# Eingangsstufe.net
KiCad netlist of a schematic drawn in Altium Designer
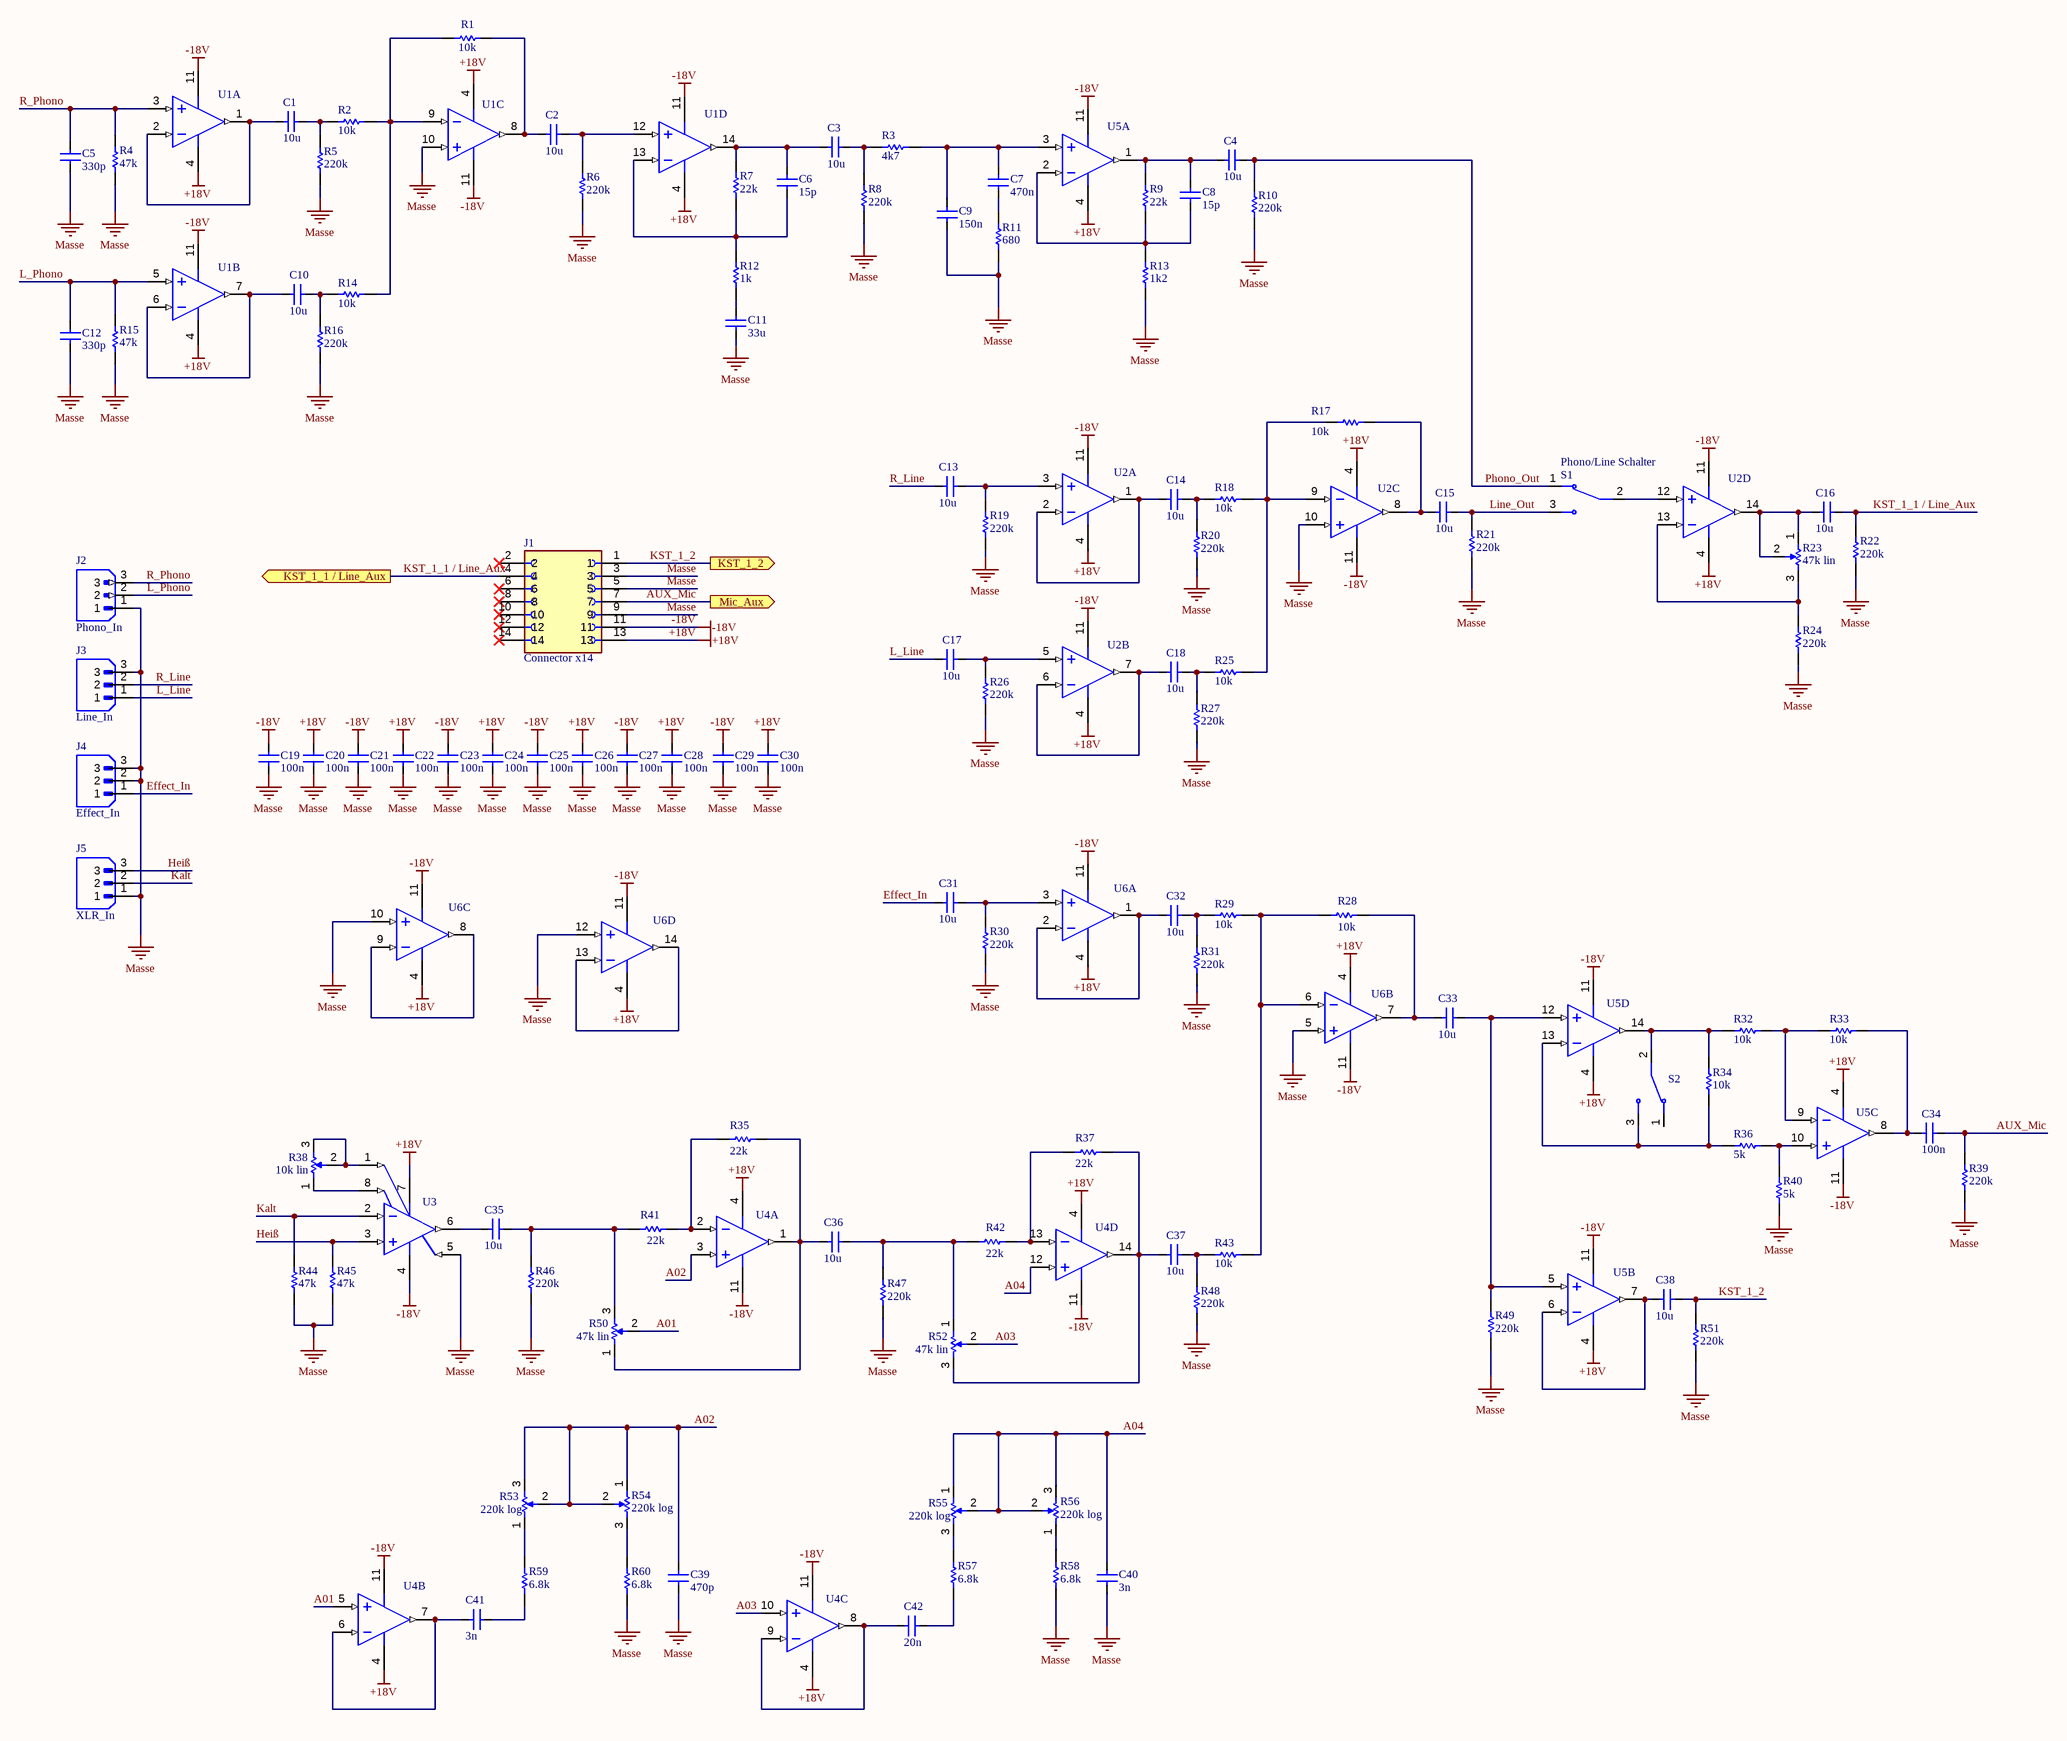
[diagram p0: Eingangsstufe.SchDoc]

(export (version "E")
  (design (tool "Eeschema 10.0.6"))
  (components
    (comp (ref "C1")
      (value "10u")
      (footprint "0805")
      (description "0805 Kondensator")
      (libsource (lib "Bauteile") (part "0805 Kondensator"))
    )
    (comp (ref "C2")
      (value "10u")
      (footprint "0805")
      (description "0805 Kondensator")
      (libsource (lib "Bauteile") (part "0805 Kondensator"))
    )
    (comp (ref "C3")
      (value "10u")
      (footprint "0805")
      (description "0805 Kondensator")
      (libsource (lib "Bauteile") (part "0805 Kondensator"))
    )
    (comp (ref "C4")
      (value "10u")
      (footprint "0805")
      (description "0805 Kondensator")
      (libsource (lib "Bauteile") (part "0805 Kondensator"))
    )
    (comp (ref "C5")
      (value "330p")
      (footprint "0805")
      (description "0805 Kondensator")
      (libsource (lib "Bauteile") (part "0805 Kondensator"))
    )
    (comp (ref "C6")
      (value "15p")
      (footprint "0805")
      (description "0805 Kondensator")
      (libsource (lib "Bauteile") (part "0805 Kondensator"))
    )
    (comp (ref "C7")
      (value "470n")
      (footprint "0805")
      (description "0805 Kondensator")
      (libsource (lib "Bauteile") (part "0805 Kondensator"))
    )
    (comp (ref "C8")
      (value "15p")
      (footprint "0805")
      (description "0805 Kondensator")
      (libsource (lib "Bauteile") (part "0805 Kondensator"))
    )
    (comp (ref "C9")
      (value "150n")
      (footprint "0805")
      (description "0805 Kondensator")
      (libsource (lib "Bauteile") (part "0805 Kondensator"))
    )
    (comp (ref "C10")
      (value "10u")
      (footprint "0805")
      (description "0805 Kondensator")
      (libsource (lib "Bauteile") (part "0805 Kondensator"))
    )
    (comp (ref "C11")
      (value "33u")
      (footprint "0805")
      (description "0805 Kondensator")
      (libsource (lib "Bauteile") (part "0805 Kondensator"))
    )
    (comp (ref "C12")
      (value "330p")
      (footprint "0805")
      (description "0805 Kondensator")
      (libsource (lib "Bauteile") (part "0805 Kondensator"))
    )
    (comp (ref "C13")
      (value "10u")
      (footprint "0805")
      (description "0805 Kondensator")
      (libsource (lib "Bauteile") (part "0805 Kondensator"))
    )
    (comp (ref "C14")
      (value "10u")
      (footprint "0805")
      (description "0805 Kondensator")
      (libsource (lib "Bauteile") (part "0805 Kondensator"))
    )
    (comp (ref "C15")
      (value "10u")
      (footprint "0805")
      (description "0805 Kondensator")
      (libsource (lib "Bauteile") (part "0805 Kondensator"))
    )
    (comp (ref "C16")
      (value "10u")
      (footprint "0805")
      (description "0805 Kondensator")
      (libsource (lib "Bauteile") (part "0805 Kondensator"))
    )
    (comp (ref "C17")
      (value "10u")
      (footprint "0805")
      (description "0805 Kondensator")
      (libsource (lib "Bauteile") (part "0805 Kondensator"))
    )
    (comp (ref "C18")
      (value "10u")
      (footprint "0805")
      (description "0805 Kondensator")
      (libsource (lib "Bauteile") (part "0805 Kondensator"))
    )
    (comp (ref "C19")
      (value "100n")
      (footprint "0805")
      (description "0805 Kondensator")
      (libsource (lib "Bauteile") (part "0805 Kondensator"))
    )
    (comp (ref "C20")
      (value "100n")
      (footprint "0805")
      (description "0805 Kondensator")
      (libsource (lib "Bauteile") (part "0805 Kondensator"))
    )
    (comp (ref "C21")
      (value "100n")
      (footprint "0805")
      (description "0805 Kondensator")
      (libsource (lib "Bauteile") (part "0805 Kondensator"))
    )
    (comp (ref "C22")
      (value "100n")
      (footprint "0805")
      (description "0805 Kondensator")
      (libsource (lib "Bauteile") (part "0805 Kondensator"))
    )
    (comp (ref "C23")
      (value "100n")
      (footprint "0805")
      (description "0805 Kondensator")
      (libsource (lib "Bauteile") (part "0805 Kondensator"))
    )
    (comp (ref "C24")
      (value "100n")
      (footprint "0805")
      (description "0805 Kondensator")
      (libsource (lib "Bauteile") (part "0805 Kondensator"))
    )
    (comp (ref "C25")
      (value "100n")
      (footprint "0805")
      (description "0805 Kondensator")
      (libsource (lib "Bauteile") (part "0805 Kondensator"))
    )
    (comp (ref "C26")
      (value "100n")
      (footprint "0805")
      (description "0805 Kondensator")
      (libsource (lib "Bauteile") (part "0805 Kondensator"))
    )
    (comp (ref "C27")
      (value "100n")
      (footprint "0805")
      (description "0805 Kondensator")
      (libsource (lib "Bauteile") (part "0805 Kondensator"))
    )
    (comp (ref "C28")
      (value "100n")
      (footprint "0805")
      (description "0805 Kondensator")
      (libsource (lib "Bauteile") (part "0805 Kondensator"))
    )
    (comp (ref "C29")
      (value "100n")
      (footprint "0805")
      (description "0805 Kondensator")
      (libsource (lib "Bauteile") (part "0805 Kondensator"))
    )
    (comp (ref "C30")
      (value "100n")
      (footprint "0805")
      (description "0805 Kondensator")
      (libsource (lib "Bauteile") (part "0805 Kondensator"))
    )
    (comp (ref "C31")
      (value "10u")
      (footprint "0805")
      (description "0805 Kondensator")
      (libsource (lib "Bauteile") (part "0805 Kondensator"))
    )
    (comp (ref "C32")
      (value "10u")
      (footprint "0805")
      (description "0805 Kondensator")
      (libsource (lib "Bauteile") (part "0805 Kondensator"))
    )
    (comp (ref "C33")
      (value "10u")
      (footprint "0805")
      (description "0805 Kondensator")
      (libsource (lib "Bauteile") (part "0805 Kondensator"))
    )
    (comp (ref "C34")
      (value "100n")
      (footprint "0805")
      (description "0805 Kondensator")
      (libsource (lib "Bauteile") (part "0805 Kondensator"))
    )
    (comp (ref "C35")
      (value "10u")
      (footprint "0805")
      (description "0805 Kondensator")
      (libsource (lib "Bauteile") (part "0805 Kondensator"))
    )
    (comp (ref "C36")
      (value "10u")
      (footprint "0805")
      (description "0805 Kondensator")
      (libsource (lib "Bauteile") (part "0805 Kondensator"))
    )
    (comp (ref "C37")
      (value "10u")
      (footprint "0805")
      (description "0805 Kondensator")
      (libsource (lib "Bauteile") (part "0805 Kondensator"))
    )
    (comp (ref "C38")
      (value "10u")
      (footprint "0805")
      (description "0805 Kondensator")
      (libsource (lib "Bauteile") (part "0805 Kondensator"))
    )
    (comp (ref "C39")
      (value "470p")
      (footprint "0805")
      (description "0805 Kondensator")
      (libsource (lib "Bauteile") (part "0805 Kondensator"))
    )
    (comp (ref "C40")
      (value "3n")
      (footprint "0805")
      (description "0805 Kondensator")
      (libsource (lib "Bauteile") (part "0805 Kondensator"))
    )
    (comp (ref "C41")
      (value "3n")
      (footprint "0805")
      (description "0805 Kondensator")
      (libsource (lib "Bauteile") (part "0805 Kondensator"))
    )
    (comp (ref "C42")
      (value "20n")
      (footprint "0805")
      (description "0805 Kondensator")
      (libsource (lib "Bauteile") (part "0805 Kondensator"))
    )
    (comp (ref "J1")
      (value "Connector x14")
      (footprint "Connector x14")
      (description "14 Position Header Connector Through Hole")
      (fields (field (name "MF") "Sullins Connector") (field (name "MP") "SFH11-PBPC-D07-ST-BK"))
      (libsource (lib "Bauteile") (part "Connector x14"))
    )
    (comp (ref "J2")
      (value "Phono_In")
      (footprint "Connector x3")
      (description "Connector Header Through Hole 3 position 0.100 (2.54mm)")
      (fields (field (name "MF") "JST Sales") (field (name "MP") "B3B-XH-A"))
      (libsource (lib "Bauteile") (part "Connector x3"))
    )
    (comp (ref "J3")
      (value "Line_In")
      (footprint "Connector x3")
      (description "Connector Header Through Hole 3 position 0.100 (2.54mm)")
      (fields (field (name "MF") "JST Sales") (field (name "MP") "B3B-XH-A"))
      (libsource (lib "Bauteile") (part "Connector x3"))
    )
    (comp (ref "J4")
      (value "Effect_In")
      (footprint "Connector x3")
      (description "Connector Header Through Hole 3 position 0.100 (2.54mm)")
      (fields (field (name "MF") "JST Sales") (field (name "MP") "B3B-XH-A"))
      (libsource (lib "Bauteile") (part "Connector x3"))
    )
    (comp (ref "J5")
      (value "XLR_In")
      (footprint "Connector x3")
      (description "Connector Header Through Hole 3 position 0.100 (2.54mm)")
      (fields (field (name "MF") "JST Sales") (field (name "MP") "B3B-XH-A"))
      (libsource (lib "Bauteile") (part "Connector x3"))
    )
    (comp (ref "R1")
      (value "10k")
      (footprint "0805")
      (description "0805 Widerstand")
      (libsource (lib "Bauteile") (part "0805 Widerstand"))
    )
    (comp (ref "R2")
      (value "10k")
      (footprint "0805")
      (description "0805 Widerstand")
      (libsource (lib "Bauteile") (part "0805 Widerstand"))
    )
    (comp (ref "R3")
      (value "4k7")
      (footprint "0805")
      (description "0805 Widerstand")
      (libsource (lib "Bauteile") (part "0805 Widerstand"))
    )
    (comp (ref "R4")
      (value "47k")
      (footprint "0805")
      (description "0805 Widerstand")
      (libsource (lib "Bauteile") (part "0805 Widerstand"))
    )
    (comp (ref "R5")
      (value "220k")
      (footprint "0805")
      (description "0805 Widerstand")
      (libsource (lib "Bauteile") (part "0805 Widerstand"))
    )
    (comp (ref "R6")
      (value "220k")
      (footprint "0805")
      (description "0805 Widerstand")
      (libsource (lib "Bauteile") (part "0805 Widerstand"))
    )
    (comp (ref "R7")
      (value "22k")
      (footprint "0805")
      (description "0805 Widerstand")
      (libsource (lib "Bauteile") (part "0805 Widerstand"))
    )
    (comp (ref "R8")
      (value "220k")
      (footprint "0805")
      (description "0805 Widerstand")
      (libsource (lib "Bauteile") (part "0805 Widerstand"))
    )
    (comp (ref "R9")
      (value "22k")
      (footprint "0805")
      (description "0805 Widerstand")
      (libsource (lib "Bauteile") (part "0805 Widerstand"))
    )
    (comp (ref "R10")
      (value "220k")
      (footprint "0805")
      (description "0805 Widerstand")
      (libsource (lib "Bauteile") (part "0805 Widerstand"))
    )
    (comp (ref "R11")
      (value "680")
      (footprint "0805")
      (description "0805 Widerstand")
      (libsource (lib "Bauteile") (part "0805 Widerstand"))
    )
    (comp (ref "R12")
      (value "1k")
      (footprint "0805")
      (description "0805 Widerstand")
      (libsource (lib "Bauteile") (part "0805 Widerstand"))
    )
    (comp (ref "R13")
      (value "1k2")
      (footprint "0805")
      (description "0805 Widerstand")
      (libsource (lib "Bauteile") (part "0805 Widerstand"))
    )
    (comp (ref "R14")
      (value "10k")
      (footprint "0805")
      (description "0805 Widerstand")
      (libsource (lib "Bauteile") (part "0805 Widerstand"))
    )
    (comp (ref "R15")
      (value "47k")
      (footprint "0805")
      (description "0805 Widerstand")
      (libsource (lib "Bauteile") (part "0805 Widerstand"))
    )
    (comp (ref "R16")
      (value "220k")
      (footprint "0805")
      (description "0805 Widerstand")
      (libsource (lib "Bauteile") (part "0805 Widerstand"))
    )
    (comp (ref "R17")
      (value "10k")
      (footprint "0805")
      (description "0805 Widerstand")
      (libsource (lib "Bauteile") (part "0805 Widerstand"))
    )
    (comp (ref "R18")
      (value "10k")
      (footprint "0805")
      (description "0805 Widerstand")
      (libsource (lib "Bauteile") (part "0805 Widerstand"))
    )
    (comp (ref "R19")
      (value "220k")
      (footprint "0805")
      (description "0805 Widerstand")
      (libsource (lib "Bauteile") (part "0805 Widerstand"))
    )
    (comp (ref "R20")
      (value "220k")
      (footprint "0805")
      (description "0805 Widerstand")
      (libsource (lib "Bauteile") (part "0805 Widerstand"))
    )
    (comp (ref "R21")
      (value "220k")
      (footprint "0805")
      (description "0805 Widerstand")
      (libsource (lib "Bauteile") (part "0805 Widerstand"))
    )
    (comp (ref "R22")
      (value "220k")
      (footprint "0805")
      (description "0805 Widerstand")
      (libsource (lib "Bauteile") (part "0805 Widerstand"))
    )
    (comp (ref "R23")
      (value "47k lin")
      (footprint "Connector x3")
      (description "Potentiometer")
      (libsource (lib "Bauteile") (part "Potentiometer Buchsenleiste"))
    )
    (comp (ref "R24")
      (value "220k")
      (footprint "0805")
      (description "0805 Widerstand")
      (libsource (lib "Bauteile") (part "0805 Widerstand"))
    )
    (comp (ref "R25")
      (value "10k")
      (footprint "0805")
      (description "0805 Widerstand")
      (libsource (lib "Bauteile") (part "0805 Widerstand"))
    )
    (comp (ref "R26")
      (value "220k")
      (footprint "0805")
      (description "0805 Widerstand")
      (libsource (lib "Bauteile") (part "0805 Widerstand"))
    )
    (comp (ref "R27")
      (value "220k")
      (footprint "0805")
      (description "0805 Widerstand")
      (libsource (lib "Bauteile") (part "0805 Widerstand"))
    )
    (comp (ref "R28")
      (value "10k")
      (footprint "0805")
      (description "0805 Widerstand")
      (libsource (lib "Bauteile") (part "0805 Widerstand"))
    )
    (comp (ref "R29")
      (value "10k")
      (footprint "0805")
      (description "0805 Widerstand")
      (libsource (lib "Bauteile") (part "0805 Widerstand"))
    )
    (comp (ref "R30")
      (value "220k")
      (footprint "0805")
      (description "0805 Widerstand")
      (libsource (lib "Bauteile") (part "0805 Widerstand"))
    )
    (comp (ref "R31")
      (value "220k")
      (footprint "0805")
      (description "0805 Widerstand")
      (libsource (lib "Bauteile") (part "0805 Widerstand"))
    )
    (comp (ref "R32")
      (value "10k")
      (footprint "0805")
      (description "0805 Widerstand")
      (libsource (lib "Bauteile") (part "0805 Widerstand"))
    )
    (comp (ref "R33")
      (value "10k")
      (footprint "0805")
      (description "0805 Widerstand")
      (libsource (lib "Bauteile") (part "0805 Widerstand"))
    )
    (comp (ref "R34")
      (value "10k")
      (footprint "0805")
      (description "0805 Widerstand")
      (libsource (lib "Bauteile") (part "0805 Widerstand"))
    )
    (comp (ref "R35")
      (value "22k")
      (footprint "0805")
      (description "0805 Widerstand")
      (libsource (lib "Bauteile") (part "0805 Widerstand"))
    )
    (comp (ref "R36")
      (value "5k")
      (footprint "0805")
      (description "0805 Widerstand")
      (libsource (lib "Bauteile") (part "0805 Widerstand"))
    )
    (comp (ref "R37")
      (value "22k")
      (footprint "0805")
      (description "0805 Widerstand")
      (libsource (lib "Bauteile") (part "0805 Widerstand"))
    )
    (comp (ref "R38")
      (value "10k lin")
      (footprint "Connector x3")
      (description "Potentiometer")
      (libsource (lib "Bauteile") (part "Potentiometer Buchsenleiste"))
    )
    (comp (ref "R39")
      (value "220k")
      (footprint "0805")
      (description "0805 Widerstand")
      (libsource (lib "Bauteile") (part "0805 Widerstand"))
    )
    (comp (ref "R40")
      (value "5k")
      (footprint "0805")
      (description "0805 Widerstand")
      (libsource (lib "Bauteile") (part "0805 Widerstand"))
    )
    (comp (ref "R41")
      (value "22k")
      (footprint "0805")
      (description "0805 Widerstand")
      (libsource (lib "Bauteile") (part "0805 Widerstand"))
    )
    (comp (ref "R42")
      (value "22k")
      (footprint "0805")
      (description "0805 Widerstand")
      (libsource (lib "Bauteile") (part "0805 Widerstand"))
    )
    (comp (ref "R43")
      (value "10k")
      (footprint "0805")
      (description "0805 Widerstand")
      (libsource (lib "Bauteile") (part "0805 Widerstand"))
    )
    (comp (ref "R44")
      (value "47k")
      (footprint "0805")
      (description "0805 Widerstand")
      (libsource (lib "Bauteile") (part "0805 Widerstand"))
    )
    (comp (ref "R45")
      (value "47k")
      (footprint "0805")
      (description "0805 Widerstand")
      (libsource (lib "Bauteile") (part "0805 Widerstand"))
    )
    (comp (ref "R46")
      (value "220k")
      (footprint "0805")
      (description "0805 Widerstand")
      (libsource (lib "Bauteile") (part "0805 Widerstand"))
    )
    (comp (ref "R47")
      (value "220k")
      (footprint "0805")
      (description "0805 Widerstand")
      (libsource (lib "Bauteile") (part "0805 Widerstand"))
    )
    (comp (ref "R48")
      (value "220k")
      (footprint "0805")
      (description "0805 Widerstand")
      (libsource (lib "Bauteile") (part "0805 Widerstand"))
    )
    (comp (ref "R49")
      (value "220k")
      (footprint "0805")
      (description "0805 Widerstand")
      (libsource (lib "Bauteile") (part "0805 Widerstand"))
    )
    (comp (ref "R50")
      (value "47k lin")
      (footprint "Connector x3")
      (description "Potentiometer")
      (libsource (lib "Bauteile") (part "Potentiometer Buchsenleiste"))
    )
    (comp (ref "R51")
      (value "220k")
      (footprint "0805")
      (description "0805 Widerstand")
      (libsource (lib "Bauteile") (part "0805 Widerstand"))
    )
    (comp (ref "R52")
      (value "47k lin")
      (footprint "Connector x3")
      (description "Potentiometer")
      (libsource (lib "Bauteile") (part "Potentiometer Buchsenleiste"))
    )
    (comp (ref "R53")
      (value "220k log")
      (footprint "Connector x3")
      (description "Potentiometer")
      (libsource (lib "Bauteile") (part "Potentiometer Buchsenleiste"))
    )
    (comp (ref "R54")
      (value "220k log")
      (footprint "Connector x3")
      (description "Potentiometer")
      (libsource (lib "Bauteile") (part "Potentiometer Buchsenleiste"))
    )
    (comp (ref "R55")
      (value "220k log")
      (footprint "Connector x3")
      (description "Potentiometer")
      (libsource (lib "Bauteile") (part "Potentiometer Buchsenleiste"))
    )
    (comp (ref "R56")
      (value "220k log")
      (footprint "Connector x3")
      (description "Potentiometer")
      (libsource (lib "Bauteile") (part "Potentiometer Buchsenleiste"))
    )
    (comp (ref "R57")
      (value "6.8k")
      (footprint "0805")
      (description "0805 Widerstand")
      (libsource (lib "Bauteile") (part "0805 Widerstand"))
    )
    (comp (ref "R58")
      (value "6.8k")
      (footprint "0805")
      (description "0805 Widerstand")
      (libsource (lib "Bauteile") (part "0805 Widerstand"))
    )
    (comp (ref "R59")
      (value "6.8k")
      (footprint "0805")
      (description "0805 Widerstand")
      (libsource (lib "Bauteile") (part "0805 Widerstand"))
    )
    (comp (ref "R60")
      (value "6.8k")
      (footprint "0805")
      (description "0805 Widerstand")
      (libsource (lib "Bauteile") (part "0805 Widerstand"))
    )
    (comp (ref "S1")
      (value "Phono/Line Schalter")
      (footprint "Connector x3")
      (description "Toggle Switch SPDT Through Hole")
      (fields (field (name "MP") "100SP1T1B4M2QE"))
      (libsource (lib "Bauteile") (part "Schalter Buchsenleiste"))
    )
    (comp (ref "S2")
      (value "Schalter Buchsenleiste")
      (footprint "Connector x3")
      (description "Toggle Switch SPDT Through Hole")
      (fields (field (name "MP") "100SP1T1B4M2QE"))
      (libsource (lib "Bauteile") (part "Schalter Buchsenleiste"))
    )
    (comp (ref "U1")
      (value "OPA4134UA")
      (footprint "DIP14 IC Socket")
      (fields (field (name "MANUFACTURER") "Texas Instruments"))
      (libsource (lib "Bauteile") (part "SOIC OPA4134UA"))
    )
    (comp (ref "U2")
      (value "OPA4134UA")
      (footprint "DIP14 IC Socket")
      (fields (field (name "MANUFACTURER") "Texas Instruments"))
      (libsource (lib "Bauteile") (part "SOIC OPA4134UA"))
    )
    (comp (ref "U3")
      (value "INA128U")
      (footprint "INA 128")
      (fields (field (name "MANUFACTURER") "Texas Instruments"))
      (libsource (lib "Bauteile") (part "INA 128"))
    )
    (comp (ref "U4")
      (value "OPA4134UA")
      (footprint "DIP14 IC Socket")
      (fields (field (name "MANUFACTURER") "Texas Instruments"))
      (libsource (lib "Bauteile") (part "SOIC OPA4134UA"))
    )
    (comp (ref "U5")
      (value "OPA4134UA")
      (footprint "DIP14 IC Socket")
      (fields (field (name "MANUFACTURER") "Texas Instruments"))
      (libsource (lib "Bauteile") (part "SOIC OPA4134UA"))
    )
    (comp (ref "U6")
      (value "OPA4134UA")
      (footprint "DIP14 IC Socket")
      (fields (field (name "MANUFACTURER") "Texas Instruments"))
      (libsource (lib "Bauteile") (part "SOIC OPA4134UA"))
    )
  )
  (nets
    (net (code "1") (name "+18V") (class "Default")
      (node (ref "C20") (pin "2") (pinfunction "2_2") (pintype "passive"))
      (node (ref "C22") (pin "2") (pinfunction "2_2") (pintype "passive"))
      (node (ref "C24") (pin "2") (pinfunction "2_2") (pintype "passive"))
      (node (ref "C26") (pin "2") (pinfunction "2_2") (pintype "passive"))
      (node (ref "C28") (pin "2") (pinfunction "2_2") (pintype "passive"))
      (node (ref "C30") (pin "2") (pinfunction "2_2") (pintype "passive"))
      (node (ref "J1") (pin "13") (pinfunction "13_13") (pintype "passive"))
      (node (ref "U1") (pin "4") (pinfunction "V+_4") (pintype "power_in"))
      (node (ref "U2") (pin "4") (pinfunction "V+_4") (pintype "power_in"))
      (node (ref "U3") (pin "7") (pinfunction "V+_7") (pintype "power_in"))
      (node (ref "U4") (pin "4") (pinfunction "V+_4") (pintype "power_in"))
      (node (ref "U5") (pin "4") (pinfunction "V+_4") (pintype "power_in"))
      (node (ref "U6") (pin "4") (pinfunction "V+_4") (pintype "power_in"))
    )
    (net (code "2") (name "-18V") (class "Default")
      (node (ref "C19") (pin "2") (pinfunction "2_2") (pintype "passive"))
      (node (ref "C21") (pin "2") (pinfunction "2_2") (pintype "passive"))
      (node (ref "C23") (pin "2") (pinfunction "2_2") (pintype "passive"))
      (node (ref "C25") (pin "2") (pinfunction "2_2") (pintype "passive"))
      (node (ref "C27") (pin "2") (pinfunction "2_2") (pintype "passive"))
      (node (ref "C29") (pin "2") (pinfunction "2_2") (pintype "passive"))
      (node (ref "J1") (pin "11") (pinfunction "11_11") (pintype "passive"))
      (node (ref "U1") (pin "11") (pinfunction "V-_11") (pintype "power_in"))
      (node (ref "U2") (pin "11") (pinfunction "V-_11") (pintype "power_in"))
      (node (ref "U3") (pin "4") (pinfunction "V-_4") (pintype "power_in"))
      (node (ref "U4") (pin "11") (pinfunction "V-_11") (pintype "power_in"))
      (node (ref "U5") (pin "11") (pinfunction "V-_11") (pintype "power_in"))
      (node (ref "U6") (pin "11") (pinfunction "V-_11") (pintype "power_in"))
    )
    (net (code "3") (name "/A01") (class "Default")
      (node (ref "R50") (pin "2") (pinfunction "2_2") (pintype "passive"))
      (node (ref "U4") (pin "5") (pinfunction "IN_B+_5") (pintype "input"))
    )
    (net (code "4") (name "/A02") (class "Default")
      (node (ref "C39") (pin "2") (pinfunction "2_2") (pintype "passive"))
      (node (ref "R53") (pin "2") (pinfunction "2_2") (pintype "passive"))
      (node (ref "R53") (pin "3") (pinfunction "3_3") (pintype "passive"))
      (node (ref "R54") (pin "1") (pinfunction "1_1") (pintype "passive"))
      (node (ref "R54") (pin "2") (pinfunction "2_2") (pintype "passive"))
      (node (ref "U4") (pin "3") (pinfunction "IN_A+_3") (pintype "input"))
    )
    (net (code "5") (name "/A03") (class "Default")
      (node (ref "R52") (pin "2") (pinfunction "2_2") (pintype "passive"))
      (node (ref "U4") (pin "10") (pinfunction "IN_C+_10") (pintype "input"))
    )
    (net (code "6") (name "/A04") (class "Default")
      (node (ref "C40") (pin "1") (pinfunction "1_1") (pintype "passive"))
      (node (ref "R55") (pin "1") (pinfunction "1_1") (pintype "passive"))
      (node (ref "R55") (pin "2") (pinfunction "2_2") (pintype "passive"))
      (node (ref "R56") (pin "2") (pinfunction "2_2") (pintype "passive"))
      (node (ref "R56") (pin "3") (pinfunction "3_3") (pintype "passive"))
      (node (ref "U4") (pin "12") (pinfunction "IN_D+_12") (pintype "input"))
    )
    (net (code "7") (name "/AUX_Mic") (class "Default")
      (node (ref "C34") (pin "2") (pinfunction "2_2") (pintype "passive"))
      (node (ref "J1") (pin "7") (pinfunction "7_7") (pintype "passive"))
      (node (ref "R39") (pin "2") (pinfunction "2_2") (pintype "passive"))
    )
    (net (code "8") (name "/Effect_In") (class "Default")
      (node (ref "C31") (pin "1") (pinfunction "1_1") (pintype "passive"))
      (node (ref "J4") (pin "1") (pinfunction "1_1") (pintype "passive"))
    )
    (net (code "9") (name "/Heiß") (class "Default")
      (node (ref "J5") (pin "3") (pinfunction "3_3") (pintype "passive"))
      (node (ref "R45") (pin "2") (pinfunction "2_2") (pintype "passive"))
      (node (ref "U3") (pin "3") (pinfunction "VIN+_3") (pintype "input"))
    )
    (net (code "10") (name "/KST_1_1 {slash} Line_Aux") (class "Default")
      (node (ref "C16") (pin "2") (pinfunction "2_2") (pintype "passive"))
      (node (ref "J1") (pin "4") (pinfunction "4_4") (pintype "passive"))
      (node (ref "R22") (pin "2") (pinfunction "2_2") (pintype "passive"))
    )
    (net (code "11") (name "/KST_1_2") (class "Default")
      (node (ref "C38") (pin "2") (pinfunction "2_2") (pintype "passive"))
      (node (ref "J1") (pin "1") (pinfunction "1_1") (pintype "passive"))
      (node (ref "R51") (pin "2") (pinfunction "2_2") (pintype "passive"))
    )
    (net (code "12") (name "/Kalt") (class "Default")
      (node (ref "J5") (pin "2") (pinfunction "2_2") (pintype "passive"))
      (node (ref "R44") (pin "2") (pinfunction "2_2") (pintype "passive"))
      (node (ref "U3") (pin "2") (pinfunction "VIN-_2") (pintype "input"))
    )
    (net (code "13") (name "/L_Line") (class "Default")
      (node (ref "C17") (pin "2") (pinfunction "2_2") (pintype "passive"))
      (node (ref "J3") (pin "1") (pinfunction "1_1") (pintype "passive"))
    )
    (net (code "14") (name "/L_Phono") (class "Default")
      (node (ref "C12") (pin "2") (pinfunction "2_2") (pintype "passive"))
      (node (ref "J2") (pin "2") (pinfunction "2_2") (pintype "passive"))
      (node (ref "R15") (pin "2") (pinfunction "2_2") (pintype "passive"))
      (node (ref "U1") (pin "5") (pinfunction "IN_B+_5") (pintype "input"))
    )
    (net (code "15") (name "/Line_Out") (class "Default")
      (node (ref "C15") (pin "1") (pinfunction "1_1") (pintype "passive"))
      (node (ref "R21") (pin "2") (pinfunction "2_2") (pintype "passive"))
      (node (ref "S1") (pin "3") (pinfunction "3_3") (pintype "passive"))
    )
    (net (code "16") (name "/Phono_Out") (class "Default")
      (node (ref "C4") (pin "1") (pinfunction "1_1") (pintype "passive"))
      (node (ref "R10") (pin "2") (pinfunction "2_2") (pintype "passive"))
      (node (ref "S1") (pin "1") (pinfunction "1_1") (pintype "passive"))
    )
    (net (code "17") (name "/R_Line") (class "Default")
      (node (ref "C13") (pin "1") (pinfunction "1_1") (pintype "passive"))
      (node (ref "J3") (pin "2") (pinfunction "2_2") (pintype "passive"))
    )
    (net (code "18") (name "/R_Phono") (class "Default")
      (node (ref "C5") (pin "2") (pinfunction "2_2") (pintype "passive"))
      (node (ref "J2") (pin "3") (pinfunction "3_3") (pintype "passive"))
      (node (ref "R4") (pin "2") (pinfunction "2_2") (pintype "passive"))
      (node (ref "U1") (pin "3") (pinfunction "IN_A+_3") (pintype "input"))
    )
    (net (code "19") (name "Masse") (class "Default")
      (node (ref "C11") (pin "1") (pinfunction "1_1") (pintype "passive"))
      (node (ref "C12") (pin "1") (pinfunction "1_1") (pintype "passive"))
      (node (ref "C19") (pin "1") (pinfunction "1_1") (pintype "passive"))
      (node (ref "C20") (pin "1") (pinfunction "1_1") (pintype "passive"))
      (node (ref "C21") (pin "1") (pinfunction "1_1") (pintype "passive"))
      (node (ref "C22") (pin "1") (pinfunction "1_1") (pintype "passive"))
      (node (ref "C23") (pin "1") (pinfunction "1_1") (pintype "passive"))
      (node (ref "C24") (pin "1") (pinfunction "1_1") (pintype "passive"))
      (node (ref "C25") (pin "1") (pinfunction "1_1") (pintype "passive"))
      (node (ref "C26") (pin "1") (pinfunction "1_1") (pintype "passive"))
      (node (ref "C27") (pin "1") (pinfunction "1_1") (pintype "passive"))
      (node (ref "C28") (pin "1") (pinfunction "1_1") (pintype "passive"))
      (node (ref "C29") (pin "1") (pinfunction "1_1") (pintype "passive"))
      (node (ref "C30") (pin "1") (pinfunction "1_1") (pintype "passive"))
      (node (ref "C39") (pin "1") (pinfunction "1_1") (pintype "passive"))
      (node (ref "C40") (pin "2") (pinfunction "2_2") (pintype "passive"))
      (node (ref "C5") (pin "1") (pinfunction "1_1") (pintype "passive"))
      (node (ref "C9") (pin "1") (pinfunction "1_1") (pintype "passive"))
      (node (ref "J1") (pin "3") (pinfunction "3_3") (pintype "passive"))
      (node (ref "J1") (pin "5") (pinfunction "5_5") (pintype "passive"))
      (node (ref "J1") (pin "9") (pinfunction "9_9") (pintype "passive"))
      (node (ref "J2") (pin "1") (pinfunction "1_1") (pintype "passive"))
      (node (ref "J3") (pin "3") (pinfunction "3_3") (pintype "passive"))
      (node (ref "J4") (pin "2") (pinfunction "2_2") (pintype "passive"))
      (node (ref "J4") (pin "3") (pinfunction "3_3") (pintype "passive"))
      (node (ref "J5") (pin "1") (pinfunction "1_1") (pintype "passive"))
      (node (ref "R10") (pin "1") (pinfunction "1_1") (pintype "passive"))
      (node (ref "R11") (pin "1") (pinfunction "1_1") (pintype "passive"))
      (node (ref "R13") (pin "1") (pinfunction "1_1") (pintype "passive"))
      (node (ref "R15") (pin "1") (pinfunction "1_1") (pintype "passive"))
      (node (ref "R16") (pin "2") (pinfunction "2_2") (pintype "passive"))
      (node (ref "R19") (pin "1") (pinfunction "1_1") (pintype "passive"))
      (node (ref "R20") (pin "2") (pinfunction "2_2") (pintype "passive"))
      (node (ref "R21") (pin "1") (pinfunction "1_1") (pintype "passive"))
      (node (ref "R22") (pin "1") (pinfunction "1_1") (pintype "passive"))
      (node (ref "R24") (pin "1") (pinfunction "1_1") (pintype "passive"))
      (node (ref "R26") (pin "1") (pinfunction "1_1") (pintype "passive"))
      (node (ref "R27") (pin "2") (pinfunction "2_2") (pintype "passive"))
      (node (ref "R30") (pin "1") (pinfunction "1_1") (pintype "passive"))
      (node (ref "R31") (pin "2") (pinfunction "2_2") (pintype "passive"))
      (node (ref "R39") (pin "1") (pinfunction "1_1") (pintype "passive"))
      (node (ref "R4") (pin "1") (pinfunction "1_1") (pintype "passive"))
      (node (ref "R40") (pin "1") (pinfunction "1_1") (pintype "passive"))
      (node (ref "R44") (pin "1") (pinfunction "1_1") (pintype "passive"))
      (node (ref "R45") (pin "1") (pinfunction "1_1") (pintype "passive"))
      (node (ref "R46") (pin "1") (pinfunction "1_1") (pintype "passive"))
      (node (ref "R47") (pin "1") (pinfunction "1_1") (pintype "passive"))
      (node (ref "R48") (pin "2") (pinfunction "2_2") (pintype "passive"))
      (node (ref "R49") (pin "1") (pinfunction "1_1") (pintype "passive"))
      (node (ref "R5") (pin "2") (pinfunction "2_2") (pintype "passive"))
      (node (ref "R51") (pin "1") (pinfunction "1_1") (pintype "passive"))
      (node (ref "R58") (pin "2") (pinfunction "2_2") (pintype "passive"))
      (node (ref "R6") (pin "2") (pinfunction "2_2") (pintype "passive"))
      (node (ref "R60") (pin "1") (pinfunction "1_1") (pintype "passive"))
      (node (ref "R8") (pin "1") (pinfunction "1_1") (pintype "passive"))
      (node (ref "U1") (pin "10") (pinfunction "IN_C+_10") (pintype "input"))
      (node (ref "U2") (pin "10") (pinfunction "IN_C+_10") (pintype "input"))
      (node (ref "U3") (pin "5") (pinfunction "REF_5") (pintype "input"))
      (node (ref "U6") (pin "10") (pinfunction "IN_C+_10") (pintype "input"))
      (node (ref "U6") (pin "12") (pinfunction "IN_D+_12") (pintype "input"))
      (node (ref "U6") (pin "5") (pinfunction "IN_B+_5") (pintype "input"))
    )
    (net (code "20") (name "Net-(C1-Pad1)") (class "Default")
      (node (ref "C1") (pin "1") (pinfunction "1_1") (pintype "passive"))
      (node (ref "R2") (pin "2") (pinfunction "2_2") (pintype "passive"))
      (node (ref "R5") (pin "1") (pinfunction "1_1") (pintype "passive"))
    )
    (net (code "21") (name "Net-(C3-Pad1)") (class "Default")
      (node (ref "C3") (pin "1") (pinfunction "1_1") (pintype "passive"))
      (node (ref "R3") (pin "2") (pinfunction "2_2") (pintype "passive"))
      (node (ref "R8") (pin "2") (pinfunction "2_2") (pintype "passive"))
    )
    (net (code "22") (name "Net-(C7-Pad1)") (class "Default")
      (node (ref "C7") (pin "1") (pinfunction "1_1") (pintype "passive"))
      (node (ref "R11") (pin "2") (pinfunction "2_2") (pintype "passive"))
    )
    (net (code "23") (name "Net-(C10-Pad1)") (class "Default")
      (node (ref "C10") (pin "1") (pinfunction "1_1") (pintype "passive"))
      (node (ref "R14") (pin "2") (pinfunction "2_2") (pintype "passive"))
      (node (ref "R16") (pin "1") (pinfunction "1_1") (pintype "passive"))
    )
    (net (code "24") (name "Net-(C11-Pad2)") (class "Default")
      (node (ref "C11") (pin "2") (pinfunction "2_2") (pintype "passive"))
      (node (ref "R12") (pin "1") (pinfunction "1_1") (pintype "passive"))
    )
    (net (code "25") (name "Net-(C14-Pad1)") (class "Default")
      (node (ref "C14") (pin "1") (pinfunction "1_1") (pintype "passive"))
      (node (ref "R18") (pin "2") (pinfunction "2_2") (pintype "passive"))
      (node (ref "R20") (pin "1") (pinfunction "1_1") (pintype "passive"))
    )
    (net (code "26") (name "Net-(C18-Pad1)") (class "Default")
      (node (ref "C18") (pin "1") (pinfunction "1_1") (pintype "passive"))
      (node (ref "R25") (pin "2") (pinfunction "2_2") (pintype "passive"))
      (node (ref "R27") (pin "1") (pinfunction "1_1") (pintype "passive"))
    )
    (net (code "27") (name "Net-(C32-Pad1)") (class "Default")
      (node (ref "C32") (pin "1") (pinfunction "1_1") (pintype "passive"))
      (node (ref "R29") (pin "2") (pinfunction "2_2") (pintype "passive"))
      (node (ref "R31") (pin "1") (pinfunction "1_1") (pintype "passive"))
    )
    (net (code "28") (name "Net-(C35-Pad2)") (class "Default")
      (node (ref "C35") (pin "2") (pinfunction "2_2") (pintype "passive"))
      (node (ref "R41") (pin "1") (pinfunction "1_1") (pintype "passive"))
      (node (ref "R46") (pin "2") (pinfunction "2_2") (pintype "passive"))
      (node (ref "R50") (pin "3") (pinfunction "3_3") (pintype "passive"))
    )
    (net (code "29") (name "Net-(C36-Pad2)") (class "Default")
      (node (ref "C36") (pin "2") (pinfunction "2_2") (pintype "passive"))
      (node (ref "R42") (pin "1") (pinfunction "1_1") (pintype "passive"))
      (node (ref "R47") (pin "2") (pinfunction "2_2") (pintype "passive"))
      (node (ref "R52") (pin "1") (pinfunction "1_1") (pintype "passive"))
    )
    (net (code "30") (name "Net-(C37-Pad1)") (class "Default")
      (node (ref "C37") (pin "1") (pinfunction "1_1") (pintype "passive"))
      (node (ref "R43") (pin "2") (pinfunction "2_2") (pintype "passive"))
      (node (ref "R48") (pin "1") (pinfunction "1_1") (pintype "passive"))
    )
    (net (code "31") (name "Net-(C41-Pad2)") (class "Default")
      (node (ref "C41") (pin "2") (pinfunction "2_2") (pintype "passive"))
      (node (ref "R59") (pin "1") (pinfunction "1_1") (pintype "passive"))
    )
    (net (code "32") (name "Net-(C42-Pad1)") (class "Default")
      (node (ref "C42") (pin "1") (pinfunction "1_1") (pintype "passive"))
      (node (ref "R57") (pin "2") (pinfunction "2_2") (pintype "passive"))
    )
    (net (code "33") (name "Net-(R38-Pad1)") (class "Default")
      (node (ref "R38") (pin "1") (pinfunction "1_1") (pintype "passive"))
      (node (ref "U3") (pin "8") (pinfunction "RG_8") (pintype "input"))
    )
    (net (code "34") (name "Net-(R38-Pad2)") (class "Default")
      (node (ref "R38") (pin "2") (pinfunction "2_2") (pintype "passive"))
      (node (ref "R38") (pin "3") (pinfunction "3_3") (pintype "passive"))
      (node (ref "U3") (pin "1") (pinfunction "RG_1") (pintype "input"))
    )
    (net (code "35") (name "Net-(R53-Pad1)") (class "Default")
      (node (ref "R53") (pin "1") (pinfunction "1_1") (pintype "passive"))
      (node (ref "R59") (pin "2") (pinfunction "2_2") (pintype "passive"))
    )
    (net (code "36") (name "Net-(R54-Pad3)") (class "Default")
      (node (ref "R54") (pin "3") (pinfunction "3_3") (pintype "passive"))
      (node (ref "R60") (pin "2") (pinfunction "2_2") (pintype "passive"))
    )
    (net (code "37") (name "Net-(R55-Pad3)") (class "Default")
      (node (ref "R55") (pin "3") (pinfunction "3_3") (pintype "passive"))
      (node (ref "R57") (pin "1") (pinfunction "1_1") (pintype "passive"))
    )
    (net (code "38") (name "Net-(R56-Pad1)") (class "Default")
      (node (ref "R56") (pin "1") (pinfunction "1_1") (pintype "passive"))
      (node (ref "R58") (pin "1") (pinfunction "1_1") (pintype "passive"))
    )
    (net (code "39") (name "Net-(U1A-IN_A-)") (class "Default")
      (node (ref "C1") (pin "2") (pinfunction "2_2") (pintype "passive"))
      (node (ref "U1") (pin "1") (pinfunction "OUT_A_1") (pintype "output"))
      (node (ref "U1") (pin "2") (pinfunction "IN_A-_2") (pintype "input"))
    )
    (net (code "40") (name "Net-(U1B-IN_B-)") (class "Default")
      (node (ref "C10") (pin "2") (pinfunction "2_2") (pintype "passive"))
      (node (ref "U1") (pin "6") (pinfunction "IN_B-_6") (pintype "input"))
      (node (ref "U1") (pin "7") (pinfunction "OUT_B_7") (pintype "output"))
    )
    (net (code "41") (name "Net-(U1C-IN_C-)") (class "Default")
      (node (ref "R1") (pin "1") (pinfunction "1_1") (pintype "passive"))
      (node (ref "R14") (pin "1") (pinfunction "1_1") (pintype "passive"))
      (node (ref "R2") (pin "1") (pinfunction "1_1") (pintype "passive"))
      (node (ref "U1") (pin "9") (pinfunction "IN_C-_9") (pintype "input"))
    )
    (net (code "42") (name "Net-(U1C-OUT_C)") (class "Default")
      (node (ref "C2") (pin "2") (pinfunction "2_2") (pintype "passive"))
      (node (ref "R1") (pin "2") (pinfunction "2_2") (pintype "passive"))
      (node (ref "U1") (pin "8") (pinfunction "OUT_C_8") (pintype "output"))
    )
    (net (code "43") (name "Net-(U1D-IN_D+)") (class "Default")
      (node (ref "C2") (pin "1") (pinfunction "1_1") (pintype "passive"))
      (node (ref "R6") (pin "1") (pinfunction "1_1") (pintype "passive"))
      (node (ref "U1") (pin "12") (pinfunction "IN_D+_12") (pintype "input"))
    )
    (net (code "44") (name "Net-(U1D-IN_D-)") (class "Default")
      (node (ref "C6") (pin "1") (pinfunction "1_1") (pintype "passive"))
      (node (ref "R12") (pin "2") (pinfunction "2_2") (pintype "passive"))
      (node (ref "R7") (pin "1") (pinfunction "1_1") (pintype "passive"))
      (node (ref "U1") (pin "13") (pinfunction "IN_D-_13") (pintype "input"))
    )
    (net (code "45") (name "Net-(U1D-OUT_D)") (class "Default")
      (node (ref "C3") (pin "2") (pinfunction "2_2") (pintype "passive"))
      (node (ref "C6") (pin "2") (pinfunction "2_2") (pintype "passive"))
      (node (ref "R7") (pin "2") (pinfunction "2_2") (pintype "passive"))
      (node (ref "U1") (pin "14") (pinfunction "OUT_D_14") (pintype "output"))
    )
    (net (code "46") (name "Net-(U2A-IN_A+)") (class "Default")
      (node (ref "C13") (pin "2") (pinfunction "2_2") (pintype "passive"))
      (node (ref "R19") (pin "2") (pinfunction "2_2") (pintype "passive"))
      (node (ref "U2") (pin "3") (pinfunction "IN_A+_3") (pintype "input"))
    )
    (net (code "47") (name "Net-(U2A-IN_A-)") (class "Default")
      (node (ref "C14") (pin "2") (pinfunction "2_2") (pintype "passive"))
      (node (ref "U2") (pin "1") (pinfunction "OUT_A_1") (pintype "output"))
      (node (ref "U2") (pin "2") (pinfunction "IN_A-_2") (pintype "input"))
    )
    (net (code "48") (name "Net-(U2B-IN_B+)") (class "Default")
      (node (ref "C17") (pin "1") (pinfunction "1_1") (pintype "passive"))
      (node (ref "R26") (pin "2") (pinfunction "2_2") (pintype "passive"))
      (node (ref "U2") (pin "5") (pinfunction "IN_B+_5") (pintype "input"))
    )
    (net (code "49") (name "Net-(U2B-IN_B-)") (class "Default")
      (node (ref "C18") (pin "2") (pinfunction "2_2") (pintype "passive"))
      (node (ref "U2") (pin "6") (pinfunction "IN_B-_6") (pintype "input"))
      (node (ref "U2") (pin "7") (pinfunction "OUT_B_7") (pintype "output"))
    )
    (net (code "50") (name "Net-(U2C-IN_C-)") (class "Default")
      (node (ref "R17") (pin "1") (pinfunction "1_1") (pintype "passive"))
      (node (ref "R18") (pin "1") (pinfunction "1_1") (pintype "passive"))
      (node (ref "R25") (pin "1") (pinfunction "1_1") (pintype "passive"))
      (node (ref "U2") (pin "9") (pinfunction "IN_C-_9") (pintype "input"))
    )
    (net (code "51") (name "Net-(U2C-OUT_C)") (class "Default")
      (node (ref "C15") (pin "2") (pinfunction "2_2") (pintype "passive"))
      (node (ref "R17") (pin "2") (pinfunction "2_2") (pintype "passive"))
      (node (ref "U2") (pin "8") (pinfunction "OUT_C_8") (pintype "output"))
    )
    (net (code "52") (name "Net-(U2D-IN_D+)") (class "Default")
      (node (ref "S1") (pin "2") (pinfunction "2_2") (pintype "passive"))
      (node (ref "U2") (pin "12") (pinfunction "IN_D+_12") (pintype "input"))
    )
    (net (code "53") (name "Net-(U2D-IN_D-)") (class "Default")
      (node (ref "R23") (pin "3") (pinfunction "3_3") (pintype "passive"))
      (node (ref "R24") (pin "2") (pinfunction "2_2") (pintype "passive"))
      (node (ref "U2") (pin "13") (pinfunction "IN_D-_13") (pintype "input"))
    )
    (net (code "54") (name "Net-(U2D-OUT_D)") (class "Default")
      (node (ref "C16") (pin "1") (pinfunction "1_1") (pintype "passive"))
      (node (ref "R23") (pin "1") (pinfunction "1_1") (pintype "passive"))
      (node (ref "R23") (pin "2") (pinfunction "2_2") (pintype "passive"))
      (node (ref "U2") (pin "14") (pinfunction "OUT_D_14") (pintype "output"))
    )
    (net (code "55") (name "Net-(U3-VO)") (class "Default")
      (node (ref "C35") (pin "1") (pinfunction "1_1") (pintype "passive"))
      (node (ref "U3") (pin "6") (pinfunction "VO_6") (pintype "output"))
    )
    (net (code "56") (name "Net-(U4A-IN_A-)") (class "Default")
      (node (ref "R35") (pin "1") (pinfunction "1_1") (pintype "passive"))
      (node (ref "R41") (pin "2") (pinfunction "2_2") (pintype "passive"))
      (node (ref "U4") (pin "2") (pinfunction "IN_A-_2") (pintype "input"))
    )
    (net (code "57") (name "Net-(U4A-OUT_A)") (class "Default")
      (node (ref "C36") (pin "1") (pinfunction "1_1") (pintype "passive"))
      (node (ref "R35") (pin "2") (pinfunction "2_2") (pintype "passive"))
      (node (ref "R50") (pin "1") (pinfunction "1_1") (pintype "passive"))
      (node (ref "U4") (pin "1") (pinfunction "OUT_A_1") (pintype "output"))
    )
    (net (code "58") (name "Net-(U4B-IN_B-)") (class "Default")
      (node (ref "C41") (pin "1") (pinfunction "1_1") (pintype "passive"))
      (node (ref "U4") (pin "6") (pinfunction "IN_B-_6") (pintype "input"))
      (node (ref "U4") (pin "7") (pinfunction "OUT_B_7") (pintype "output"))
    )
    (net (code "59") (name "Net-(U4C-IN_C-)") (class "Default")
      (node (ref "C42") (pin "2") (pinfunction "2_2") (pintype "passive"))
      (node (ref "U4") (pin "8") (pinfunction "OUT_C_8") (pintype "output"))
      (node (ref "U4") (pin "9") (pinfunction "IN_C-_9") (pintype "input"))
    )
    (net (code "60") (name "Net-(U4D-IN_D-)") (class "Default")
      (node (ref "R37") (pin "1") (pinfunction "1_1") (pintype "passive"))
      (node (ref "R42") (pin "2") (pinfunction "2_2") (pintype "passive"))
      (node (ref "U4") (pin "13") (pinfunction "IN_D-_13") (pintype "input"))
    )
    (net (code "61") (name "Net-(U4D-OUT_D)") (class "Default")
      (node (ref "C37") (pin "2") (pinfunction "2_2") (pintype "passive"))
      (node (ref "R37") (pin "2") (pinfunction "2_2") (pintype "passive"))
      (node (ref "R52") (pin "3") (pinfunction "3_3") (pintype "passive"))
      (node (ref "U4") (pin "14") (pinfunction "OUT_D_14") (pintype "output"))
    )
    (net (code "62") (name "Net-(U5A-IN_A+)") (class "Default")
      (node (ref "C7") (pin "2") (pinfunction "2_2") (pintype "passive"))
      (node (ref "C9") (pin "2") (pinfunction "2_2") (pintype "passive"))
      (node (ref "R3") (pin "1") (pinfunction "1_1") (pintype "passive"))
      (node (ref "U5") (pin "3") (pinfunction "IN_A+_3") (pintype "input"))
    )
    (net (code "63") (name "Net-(U5A-IN_A-)") (class "Default")
      (node (ref "C8") (pin "1") (pinfunction "1_1") (pintype "passive"))
      (node (ref "R13") (pin "2") (pinfunction "2_2") (pintype "passive"))
      (node (ref "R9") (pin "1") (pinfunction "1_1") (pintype "passive"))
      (node (ref "U5") (pin "2") (pinfunction "IN_A-_2") (pintype "input"))
    )
    (net (code "64") (name "Net-(U5A-OUT_A)") (class "Default")
      (node (ref "C4") (pin "2") (pinfunction "2_2") (pintype "passive"))
      (node (ref "C8") (pin "2") (pinfunction "2_2") (pintype "passive"))
      (node (ref "R9") (pin "2") (pinfunction "2_2") (pintype "passive"))
      (node (ref "U5") (pin "1") (pinfunction "OUT_A_1") (pintype "output"))
    )
    (net (code "65") (name "Net-(U5B-IN_B+)") (class "Default")
      (node (ref "C33") (pin "2") (pinfunction "2_2") (pintype "passive"))
      (node (ref "R49") (pin "2") (pinfunction "2_2") (pintype "passive"))
      (node (ref "U5") (pin "12") (pinfunction "IN_D+_12") (pintype "input"))
      (node (ref "U5") (pin "5") (pinfunction "IN_B+_5") (pintype "input"))
    )
    (net (code "66") (name "Net-(U5B-IN_B-)") (class "Default")
      (node (ref "C38") (pin "1") (pinfunction "1_1") (pintype "passive"))
      (node (ref "U5") (pin "6") (pinfunction "IN_B-_6") (pintype "input"))
      (node (ref "U5") (pin "7") (pinfunction "OUT_B_7") (pintype "output"))
    )
    (net (code "67") (name "Net-(U5C-IN_C+)") (class "Default")
      (node (ref "R36") (pin "2") (pinfunction "2_2") (pintype "passive"))
      (node (ref "R40") (pin "2") (pinfunction "2_2") (pintype "passive"))
      (node (ref "U5") (pin "10") (pinfunction "IN_C+_10") (pintype "input"))
    )
    (net (code "68") (name "Net-(U5C-IN_C-)") (class "Default")
      (node (ref "R32") (pin "2") (pinfunction "2_2") (pintype "passive"))
      (node (ref "R33") (pin "1") (pinfunction "1_1") (pintype "passive"))
      (node (ref "U5") (pin "9") (pinfunction "IN_C-_9") (pintype "input"))
    )
    (net (code "69") (name "Net-(U5C-OUT_C)") (class "Default")
      (node (ref "C34") (pin "1") (pinfunction "1_1") (pintype "passive"))
      (node (ref "R33") (pin "2") (pinfunction "2_2") (pintype "passive"))
      (node (ref "U5") (pin "8") (pinfunction "OUT_C_8") (pintype "output"))
    )
    (net (code "70") (name "Net-(U5D-IN_D-)") (class "Default")
      (node (ref "R34") (pin "1") (pinfunction "1_1") (pintype "passive"))
      (node (ref "R36") (pin "1") (pinfunction "1_1") (pintype "passive"))
      (node (ref "S2") (pin "3") (pinfunction "3_3") (pintype "passive"))
      (node (ref "U5") (pin "13") (pinfunction "IN_D-_13") (pintype "input"))
    )
    (net (code "71") (name "Net-(U5D-OUT_D)") (class "Default")
      (node (ref "R32") (pin "1") (pinfunction "1_1") (pintype "passive"))
      (node (ref "R34") (pin "2") (pinfunction "2_2") (pintype "passive"))
      (node (ref "S2") (pin "2") (pinfunction "2_2") (pintype "passive"))
      (node (ref "U5") (pin "14") (pinfunction "OUT_D_14") (pintype "output"))
    )
    (net (code "72") (name "Net-(U6A-IN_A+)") (class "Default")
      (node (ref "C31") (pin "2") (pinfunction "2_2") (pintype "passive"))
      (node (ref "R30") (pin "2") (pinfunction "2_2") (pintype "passive"))
      (node (ref "U6") (pin "3") (pinfunction "IN_A+_3") (pintype "input"))
    )
    (net (code "73") (name "Net-(U6A-IN_A-)") (class "Default")
      (node (ref "C32") (pin "2") (pinfunction "2_2") (pintype "passive"))
      (node (ref "U6") (pin "1") (pinfunction "OUT_A_1") (pintype "output"))
      (node (ref "U6") (pin "2") (pinfunction "IN_A-_2") (pintype "input"))
    )
    (net (code "74") (name "Net-(U6B-IN_B-)") (class "Default")
      (node (ref "R28") (pin "1") (pinfunction "1_1") (pintype "passive"))
      (node (ref "R29") (pin "1") (pinfunction "1_1") (pintype "passive"))
      (node (ref "R43") (pin "1") (pinfunction "1_1") (pintype "passive"))
      (node (ref "U6") (pin "6") (pinfunction "IN_B-_6") (pintype "input"))
    )
    (net (code "75") (name "Net-(U6B-OUT_B)") (class "Default")
      (node (ref "C33") (pin "1") (pinfunction "1_1") (pintype "passive"))
      (node (ref "R28") (pin "2") (pinfunction "2_2") (pintype "passive"))
      (node (ref "U6") (pin "7") (pinfunction "OUT_B_7") (pintype "output"))
    )
    (net (code "76") (name "Net-(U6C-IN_C-)") (class "Default")
      (node (ref "U6") (pin "8") (pinfunction "OUT_C_8") (pintype "output"))
      (node (ref "U6") (pin "9") (pinfunction "IN_C-_9") (pintype "input"))
    )
    (net (code "77") (name "Net-(U6D-IN_D-)") (class "Default")
      (node (ref "U6") (pin "13") (pinfunction "IN_D-_13") (pintype "input"))
      (node (ref "U6") (pin "14") (pinfunction "OUT_D_14") (pintype "output"))
    )
    (net (code "78") (name "unconnected-(J1-Pad2)") (class "Default")
      (node (ref "J1") (pin "2") (pinfunction "2_2") (pintype "passive+no_connect"))
    )
    (net (code "79") (name "unconnected-(J1-Pad6)") (class "Default")
      (node (ref "J1") (pin "6") (pinfunction "6_6") (pintype "passive+no_connect"))
    )
    (net (code "80") (name "unconnected-(J1-Pad8)") (class "Default")
      (node (ref "J1") (pin "8") (pinfunction "8_8") (pintype "passive+no_connect"))
    )
    (net (code "81") (name "unconnected-(J1-Pad10)") (class "Default")
      (node (ref "J1") (pin "10") (pinfunction "10_10") (pintype "passive+no_connect"))
    )
    (net (code "82") (name "unconnected-(J1-Pad12)") (class "Default")
      (node (ref "J1") (pin "12") (pinfunction "12_12") (pintype "passive+no_connect"))
    )
    (net (code "83") (name "unconnected-(J1-Pad14)") (class "Default")
      (node (ref "J1") (pin "14") (pinfunction "14_14") (pintype "passive+no_connect"))
    )
    (net (code "84") (name "unconnected-(S2-Pad1)") (class "Default")
      (node (ref "S2") (pin "1") (pinfunction "1_1") (pintype "passive"))
    )
  )
)
